# x.net
KiCad netlist of a schematic drawn in EAGLE
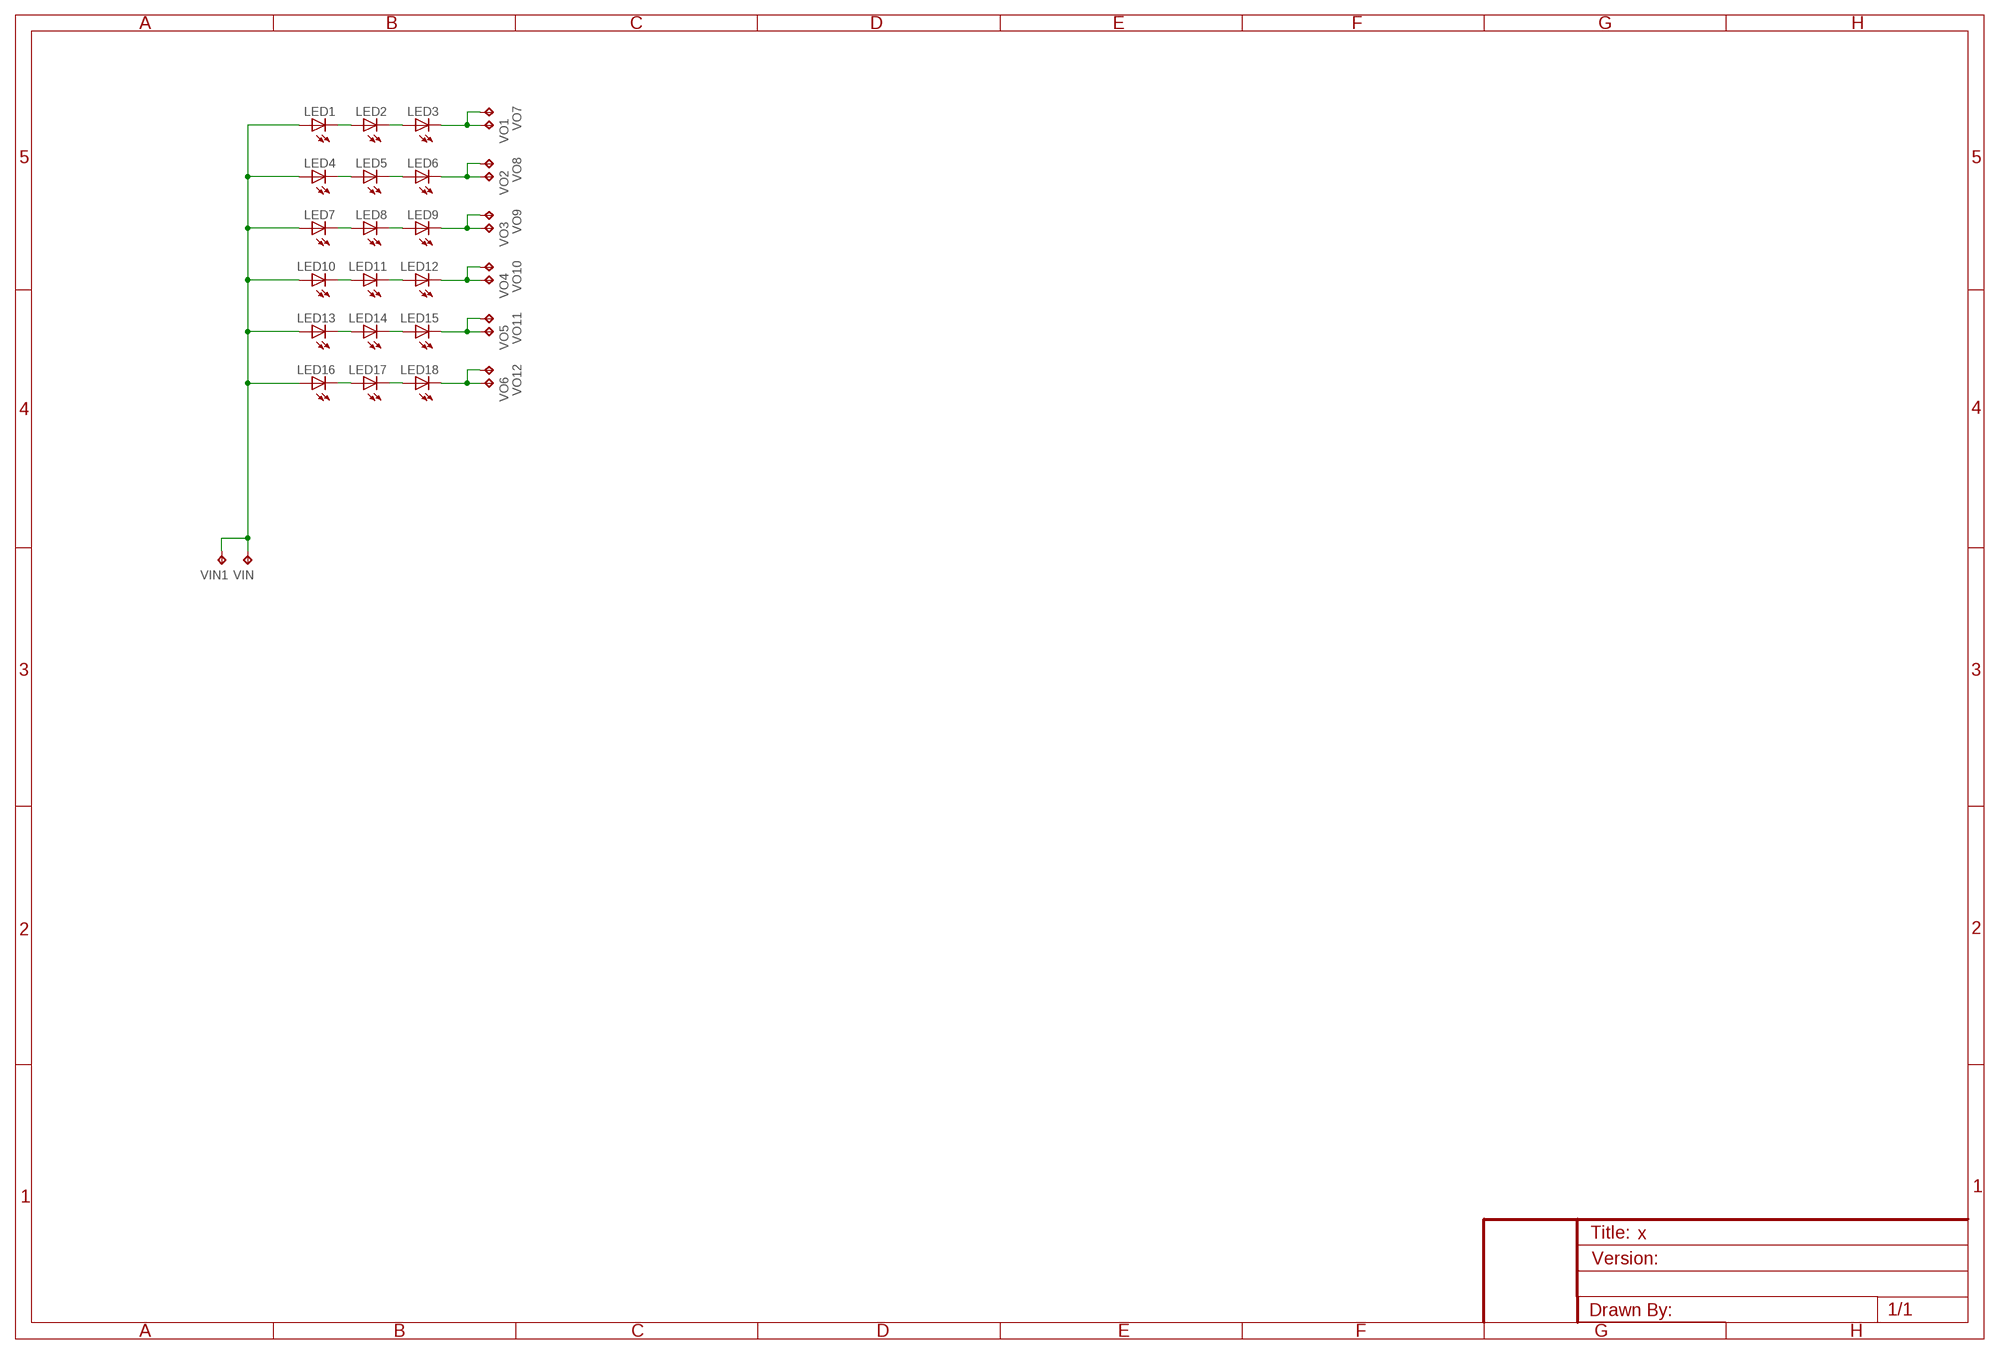
[diagram p0: schematic, sheet 1]

(export (version "E")
  (design (tool "Eeschema 10.0.6"))
  (components
    (comp (ref "LED1")
      (value "LED0805")
      (footprint "eagle-import:LED_0805")
      (libsource (lib "eagle-import") (part "LED0805"))
    )
    (comp (ref "LED2")
      (value "LED0805")
      (footprint "eagle-import:LED_0805")
      (libsource (lib "eagle-import") (part "LED0805"))
    )
    (comp (ref "LED3")
      (value "LED0805")
      (footprint "eagle-import:LED_0805")
      (libsource (lib "eagle-import") (part "LED0805"))
    )
    (comp (ref "LED4")
      (value "LED0805")
      (footprint "eagle-import:LED_0805")
      (libsource (lib "eagle-import") (part "LED0805"))
    )
    (comp (ref "LED5")
      (value "LED0805")
      (footprint "eagle-import:LED_0805")
      (libsource (lib "eagle-import") (part "LED0805"))
    )
    (comp (ref "LED6")
      (value "LED0805")
      (footprint "eagle-import:LED_0805")
      (libsource (lib "eagle-import") (part "LED0805"))
    )
    (comp (ref "LED7")
      (value "LED0805")
      (footprint "eagle-import:LED_0805")
      (libsource (lib "eagle-import") (part "LED0805"))
    )
    (comp (ref "LED8")
      (value "LED0805")
      (footprint "eagle-import:LED_0805")
      (libsource (lib "eagle-import") (part "LED0805"))
    )
    (comp (ref "LED9")
      (value "LED0805")
      (footprint "eagle-import:LED_0805")
      (libsource (lib "eagle-import") (part "LED0805"))
    )
    (comp (ref "LED10")
      (value "LED0805")
      (footprint "eagle-import:LED_0805")
      (libsource (lib "eagle-import") (part "LED0805"))
    )
    (comp (ref "LED11")
      (value "LED0805")
      (footprint "eagle-import:LED_0805")
      (libsource (lib "eagle-import") (part "LED0805"))
    )
    (comp (ref "LED12")
      (value "LED0805")
      (footprint "eagle-import:LED_0805")
      (libsource (lib "eagle-import") (part "LED0805"))
    )
    (comp (ref "LED13")
      (value "LED0805")
      (footprint "eagle-import:LED_0805")
      (libsource (lib "eagle-import") (part "LED0805"))
    )
    (comp (ref "LED14")
      (value "LED0805")
      (footprint "eagle-import:LED_0805")
      (libsource (lib "eagle-import") (part "LED0805"))
    )
    (comp (ref "LED15")
      (value "LED0805")
      (footprint "eagle-import:LED_0805")
      (libsource (lib "eagle-import") (part "LED0805"))
    )
    (comp (ref "LED16")
      (value "LED0805")
      (footprint "eagle-import:LED_0805")
      (libsource (lib "eagle-import") (part "LED0805"))
    )
    (comp (ref "LED17")
      (value "LED0805")
      (footprint "eagle-import:LED_0805")
      (libsource (lib "eagle-import") (part "LED0805"))
    )
    (comp (ref "LED18")
      (value "LED0805")
      (footprint "eagle-import:LED_0805")
      (libsource (lib "eagle-import") (part "LED0805"))
    )
    (comp (ref "VIN")
      (value "TEST_POINTPAD1-20")
      (footprint "eagle-import:P1-20")
      (libsource (lib "eagle-import") (part "TEST_POINTPAD1-20"))
    )
    (comp (ref "VIN1")
      (value "TEST_POINTPAD1-20")
      (footprint "eagle-import:P1-20")
      (libsource (lib "eagle-import") (part "TEST_POINTPAD1-20"))
    )
    (comp (ref "VO1")
      (value "TEST_POINTPAD1-20")
      (footprint "eagle-import:P1-20")
      (libsource (lib "eagle-import") (part "TEST_POINTPAD1-20"))
    )
    (comp (ref "VO2")
      (value "TEST_POINTPAD1-20")
      (footprint "eagle-import:P1-20")
      (libsource (lib "eagle-import") (part "TEST_POINTPAD1-20"))
    )
    (comp (ref "VO3")
      (value "TEST_POINTPAD1-20")
      (footprint "eagle-import:P1-20")
      (libsource (lib "eagle-import") (part "TEST_POINTPAD1-20"))
    )
    (comp (ref "VO4")
      (value "TEST_POINTPAD1-20")
      (footprint "eagle-import:P1-20")
      (libsource (lib "eagle-import") (part "TEST_POINTPAD1-20"))
    )
    (comp (ref "VO5")
      (value "TEST_POINTPAD1-20")
      (footprint "eagle-import:P1-20")
      (libsource (lib "eagle-import") (part "TEST_POINTPAD1-20"))
    )
    (comp (ref "VO6")
      (value "TEST_POINTPAD1-20")
      (footprint "eagle-import:P1-20")
      (libsource (lib "eagle-import") (part "TEST_POINTPAD1-20"))
    )
    (comp (ref "VO7")
      (value "TEST_POINTPAD1-20")
      (footprint "eagle-import:P1-20")
      (libsource (lib "eagle-import") (part "TEST_POINTPAD1-20"))
    )
    (comp (ref "VO8")
      (value "TEST_POINTPAD1-20")
      (footprint "eagle-import:P1-20")
      (libsource (lib "eagle-import") (part "TEST_POINTPAD1-20"))
    )
    (comp (ref "VO9")
      (value "TEST_POINTPAD1-20")
      (footprint "eagle-import:P1-20")
      (libsource (lib "eagle-import") (part "TEST_POINTPAD1-20"))
    )
    (comp (ref "VO10")
      (value "TEST_POINTPAD1-20")
      (footprint "eagle-import:P1-20")
      (libsource (lib "eagle-import") (part "TEST_POINTPAD1-20"))
    )
    (comp (ref "VO11")
      (value "TEST_POINTPAD1-20")
      (footprint "eagle-import:P1-20")
      (libsource (lib "eagle-import") (part "TEST_POINTPAD1-20"))
    )
    (comp (ref "VO12")
      (value "TEST_POINTPAD1-20")
      (footprint "eagle-import:P1-20")
      (libsource (lib "eagle-import") (part "TEST_POINTPAD1-20"))
    )
  )
  (nets
    (net (code "1") (name "Net-(LED1-PadA)") (class "Default")
      (node (ref "LED1") (pin "A") (pinfunction "A_A") (pintype "passive"))
      (node (ref "LED10") (pin "A") (pinfunction "A_A") (pintype "passive"))
      (node (ref "LED13") (pin "A") (pinfunction "A_A") (pintype "passive"))
      (node (ref "LED16") (pin "A") (pinfunction "A_A") (pintype "passive"))
      (node (ref "LED4") (pin "A") (pinfunction "A_A") (pintype "passive"))
      (node (ref "LED7") (pin "A") (pinfunction "A_A") (pintype "passive"))
      (node (ref "VIN") (pin "TP") (pinfunction "TP_TP") (pintype "input"))
      (node (ref "VIN1") (pin "TP") (pinfunction "TP_TP") (pintype "input"))
    )
    (net (code "2") (name "Net-(LED1-PadC)") (class "Default")
      (node (ref "LED1") (pin "C") (pinfunction "C_C") (pintype "passive"))
      (node (ref "LED2") (pin "A") (pinfunction "A_A") (pintype "passive"))
    )
    (net (code "3") (name "Net-(LED2-PadC)") (class "Default")
      (node (ref "LED2") (pin "C") (pinfunction "C_C") (pintype "passive"))
      (node (ref "LED3") (pin "A") (pinfunction "A_A") (pintype "passive"))
    )
    (net (code "4") (name "Net-(LED3-PadC)") (class "Default")
      (node (ref "LED3") (pin "C") (pinfunction "C_C") (pintype "passive"))
      (node (ref "VO1") (pin "TP") (pinfunction "TP_TP") (pintype "input"))
      (node (ref "VO7") (pin "TP") (pinfunction "TP_TP") (pintype "input"))
    )
    (net (code "5") (name "Net-(LED4-PadC)") (class "Default")
      (node (ref "LED4") (pin "C") (pinfunction "C_C") (pintype "passive"))
      (node (ref "LED5") (pin "A") (pinfunction "A_A") (pintype "passive"))
    )
    (net (code "6") (name "Net-(LED5-PadC)") (class "Default")
      (node (ref "LED5") (pin "C") (pinfunction "C_C") (pintype "passive"))
      (node (ref "LED6") (pin "A") (pinfunction "A_A") (pintype "passive"))
    )
    (net (code "7") (name "Net-(LED6-PadC)") (class "Default")
      (node (ref "LED6") (pin "C") (pinfunction "C_C") (pintype "passive"))
      (node (ref "VO2") (pin "TP") (pinfunction "TP_TP") (pintype "input"))
      (node (ref "VO8") (pin "TP") (pinfunction "TP_TP") (pintype "input"))
    )
    (net (code "8") (name "Net-(LED7-PadC)") (class "Default")
      (node (ref "LED7") (pin "C") (pinfunction "C_C") (pintype "passive"))
      (node (ref "LED8") (pin "A") (pinfunction "A_A") (pintype "passive"))
    )
    (net (code "9") (name "Net-(LED8-PadC)") (class "Default")
      (node (ref "LED8") (pin "C") (pinfunction "C_C") (pintype "passive"))
      (node (ref "LED9") (pin "A") (pinfunction "A_A") (pintype "passive"))
    )
    (net (code "10") (name "Net-(LED9-PadC)") (class "Default")
      (node (ref "LED9") (pin "C") (pinfunction "C_C") (pintype "passive"))
      (node (ref "VO3") (pin "TP") (pinfunction "TP_TP") (pintype "input"))
      (node (ref "VO9") (pin "TP") (pinfunction "TP_TP") (pintype "input"))
    )
    (net (code "11") (name "Net-(LED10-PadC)") (class "Default")
      (node (ref "LED10") (pin "C") (pinfunction "C_C") (pintype "passive"))
      (node (ref "LED11") (pin "A") (pinfunction "A_A") (pintype "passive"))
    )
    (net (code "12") (name "Net-(LED11-PadC)") (class "Default")
      (node (ref "LED11") (pin "C") (pinfunction "C_C") (pintype "passive"))
      (node (ref "LED12") (pin "A") (pinfunction "A_A") (pintype "passive"))
    )
    (net (code "13") (name "Net-(LED12-PadC)") (class "Default")
      (node (ref "LED12") (pin "C") (pinfunction "C_C") (pintype "passive"))
      (node (ref "VO10") (pin "TP") (pinfunction "TP_TP") (pintype "input"))
      (node (ref "VO4") (pin "TP") (pinfunction "TP_TP") (pintype "input"))
    )
    (net (code "14") (name "Net-(LED13-PadC)") (class "Default")
      (node (ref "LED13") (pin "C") (pinfunction "C_C") (pintype "passive"))
      (node (ref "LED14") (pin "A") (pinfunction "A_A") (pintype "passive"))
    )
    (net (code "15") (name "Net-(LED14-PadC)") (class "Default")
      (node (ref "LED14") (pin "C") (pinfunction "C_C") (pintype "passive"))
      (node (ref "LED15") (pin "A") (pinfunction "A_A") (pintype "passive"))
    )
    (net (code "16") (name "Net-(LED15-PadC)") (class "Default")
      (node (ref "LED15") (pin "C") (pinfunction "C_C") (pintype "passive"))
      (node (ref "VO11") (pin "TP") (pinfunction "TP_TP") (pintype "input"))
      (node (ref "VO5") (pin "TP") (pinfunction "TP_TP") (pintype "input"))
    )
    (net (code "17") (name "Net-(LED16-PadC)") (class "Default")
      (node (ref "LED16") (pin "C") (pinfunction "C_C") (pintype "passive"))
      (node (ref "LED17") (pin "A") (pinfunction "A_A") (pintype "passive"))
    )
    (net (code "18") (name "Net-(LED17-PadC)") (class "Default")
      (node (ref "LED17") (pin "C") (pinfunction "C_C") (pintype "passive"))
      (node (ref "LED18") (pin "A") (pinfunction "A_A") (pintype "passive"))
    )
    (net (code "19") (name "Net-(LED18-PadC)") (class "Default")
      (node (ref "LED18") (pin "C") (pinfunction "C_C") (pintype "passive"))
      (node (ref "VO12") (pin "TP") (pinfunction "TP_TP") (pintype "input"))
      (node (ref "VO6") (pin "TP") (pinfunction "TP_TP") (pintype "input"))
    )
  )
)
